# DIDV_-_Alto_Falantes.net
KiCad netlist of a schematic drawn in EAGLE
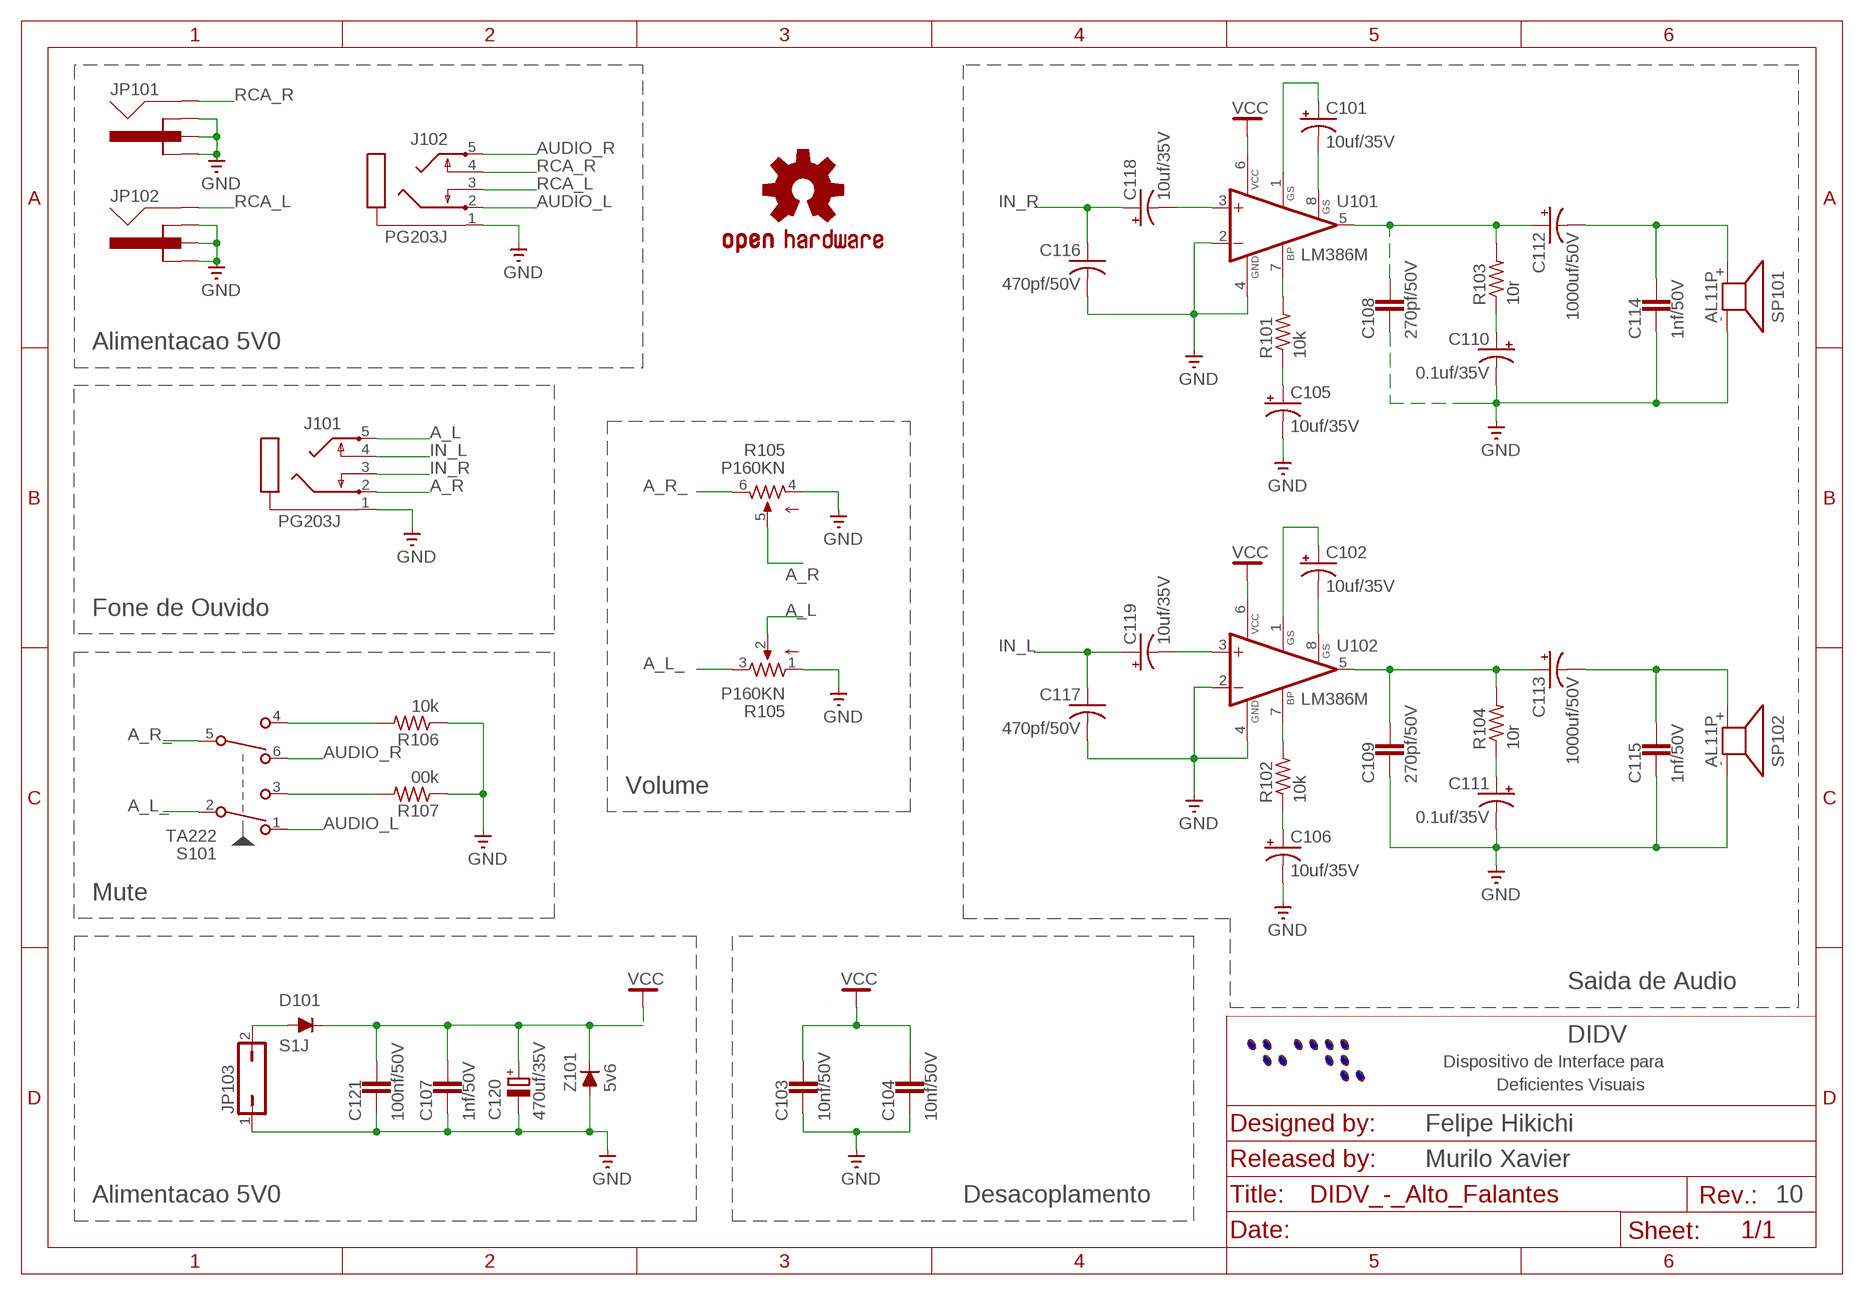
[diagram p0: schematic, sheet 1]

(export (version "E")
  (design (tool "Eeschema 10.0.6"))
  (components
    (comp (ref "C101")
      (value "10uf/35V")
      (footprint "eagle-import:E2-5")
      (libsource (lib "eagle-import") (part "CPOL-USE2-5"))
    )
    (comp (ref "C102")
      (value "10uf/35V")
      (footprint "eagle-import:E2-5")
      (libsource (lib "eagle-import") (part "CPOL-USE2-5"))
    )
    (comp (ref "C103")
      (value "10nf/50V")
      (footprint "eagle-import:C0805")
      (libsource (lib "eagle-import") (part "C-EUC0805"))
    )
    (comp (ref "C104")
      (value "10nf/50V")
      (footprint "eagle-import:C0805")
      (libsource (lib "eagle-import") (part "C-EUC0805"))
    )
    (comp (ref "C105")
      (value "10uf/35V")
      (footprint "eagle-import:E2-5")
      (libsource (lib "eagle-import") (part "CPOL-USE2-5"))
    )
    (comp (ref "C106")
      (value "10uf/35V")
      (footprint "eagle-import:E2-5")
      (libsource (lib "eagle-import") (part "CPOL-USE2-5"))
    )
    (comp (ref "C107")
      (value "1nf/50V")
      (footprint "eagle-import:C0805")
      (libsource (lib "eagle-import") (part "C-EUC0805"))
    )
    (comp (ref "C108")
      (value "270pf/50V")
      (footprint "eagle-import:C0805")
      (libsource (lib "eagle-import") (part "C-EUC0805"))
    )
    (comp (ref "C109")
      (value "270pf/50V")
      (footprint "eagle-import:C0805")
      (libsource (lib "eagle-import") (part "C-EUC0805"))
    )
    (comp (ref "C110")
      (value "0.1uf/35V")
      (footprint "eagle-import:E2-5")
      (libsource (lib "eagle-import") (part "CPOL-USE2-5"))
    )
    (comp (ref "C111")
      (value "0.1uf/35V")
      (footprint "eagle-import:E2-5")
      (libsource (lib "eagle-import") (part "CPOL-USE2-5"))
    )
    (comp (ref "C112")
      (value "1000uf/50V")
      (footprint "eagle-import:E3,5-10")
      (libsource (lib "eagle-import") (part "CPOL-USE3.5-10"))
    )
    (comp (ref "C113")
      (value "1000uf/50V")
      (footprint "eagle-import:E3,5-10")
      (libsource (lib "eagle-import") (part "CPOL-USE3.5-10"))
    )
    (comp (ref "C114")
      (value "1nf/50V")
      (footprint "eagle-import:C0805")
      (libsource (lib "eagle-import") (part "C-EUC0805"))
    )
    (comp (ref "C115")
      (value "1nf/50V")
      (footprint "eagle-import:C0805")
      (libsource (lib "eagle-import") (part "C-EUC0805"))
    )
    (comp (ref "C116")
      (value "470pf/50V")
      (footprint "eagle-import:C0603")
      (libsource (lib "eagle-import") (part "C-USC0603"))
    )
    (comp (ref "C117")
      (value "470pf/50V")
      (footprint "eagle-import:C0603")
      (libsource (lib "eagle-import") (part "C-USC0603"))
    )
    (comp (ref "C118")
      (value "10uf/35V")
      (footprint "eagle-import:E2-5")
      (libsource (lib "eagle-import") (part "CPOL-USE2-5"))
    )
    (comp (ref "C119")
      (value "10uf/35V")
      (footprint "eagle-import:E2-5")
      (libsource (lib "eagle-import") (part "CPOL-USE2-5"))
    )
    (comp (ref "C120")
      (value "470uf/35V")
      (footprint "eagle-import:E3,5-10")
      (libsource (lib "eagle-import") (part "CPOL-EUE3.5-10"))
    )
    (comp (ref "C121")
      (value "100nf/50V")
      (footprint "eagle-import:C0805")
      (libsource (lib "eagle-import") (part "C-EUC0805"))
    )
    (comp (ref "D101")
      (value "S1J")
      (footprint "eagle-import:DO214AC")
      (libsource (lib "eagle-import") (part "FS1J"))
    )
    (comp (ref "J101")
      (value "PG203J")
      (footprint "eagle-import:PG203J")
      (libsource (lib "eagle-import") (part "PG203J"))
    )
    (comp (ref "J102")
      (value "PG203J")
      (footprint "eagle-import:PG203J")
      (libsource (lib "eagle-import") (part "PG203J"))
    )
    (comp (ref "JP101")
      (value "RCA")
      (footprint "eagle-import:RCA")
      (libsource (lib "eagle-import") (part "RCA"))
    )
    (comp (ref "JP102")
      (value "RCA")
      (footprint "eagle-import:RCA")
      (libsource (lib "eagle-import") (part "RCA"))
    )
    (comp (ref "JP103")
      (value "JP1Q")
      (footprint "eagle-import:JP1")
      (libsource (lib "eagle-import") (part "JP1Q"))
    )
    (comp (ref "LOGO101")
      (value "OSHW-LOGOL")
      (footprint "eagle-import:OSHW-LOGO-L")
      (libsource (lib "eagle-import") (part "OSHW-LOGOL"))
    )
    (comp (ref "R101")
      (value "10k")
      (footprint "eagle-import:R1206")
      (libsource (lib "eagle-import") (part "R-US_R1206"))
    )
    (comp (ref "R102")
      (value "10k")
      (footprint "eagle-import:R1206")
      (libsource (lib "eagle-import") (part "R-US_R1206"))
    )
    (comp (ref "R103")
      (value "10r")
      (footprint "eagle-import:R1206")
      (libsource (lib "eagle-import") (part "R-US_R1206"))
    )
    (comp (ref "R104")
      (value "10r")
      (footprint "eagle-import:R1206")
      (libsource (lib "eagle-import") (part "R-US_R1206"))
    )
    (comp (ref "R105")
      (value "P160KN")
      (footprint "eagle-import:P160KN")
      (libsource (lib "eagle-import") (part "P160KN"))
    )
    (comp (ref "R106")
      (value "10k")
      (footprint "eagle-import:R1206")
      (libsource (lib "eagle-import") (part "R-US_R1206"))
    )
    (comp (ref "R107")
      (value "00k")
      (footprint "eagle-import:R1206")
      (libsource (lib "eagle-import") (part "R-US_R1206"))
    )
    (comp (ref "S101")
      (value "TA222")
      (footprint "eagle-import:TA222")
      (libsource (lib "eagle-import") (part "TA222"))
    )
    (comp (ref "SP101")
      (value "AL11P")
      (footprint "eagle-import:AL11P")
      (libsource (lib "eagle-import") (part "AL11P"))
    )
    (comp (ref "SP102")
      (value "AL11P")
      (footprint "eagle-import:AL11P")
      (libsource (lib "eagle-import") (part "AL11P"))
    )
    (comp (ref "U101")
      (value "LM386M")
      (footprint "eagle-import:SO08")
      (libsource (lib "eagle-import") (part "LM386M"))
    )
    (comp (ref "U102")
      (value "LM386M")
      (footprint "eagle-import:SO08")
      (libsource (lib "eagle-import") (part "LM386M"))
    )
    (comp (ref "Z101")
      (value "5v6")
      (footprint "eagle-import:SOT23")
      (libsource (lib "eagle-import") (part "BAS70"))
    )
  )
  (nets
    (net (code "1") (name "/AUDIO_L") (class "Default")
      (node (ref "J102") (pin "2") (pinfunction "2_2") (pintype "passive"))
      (node (ref "S101") (pin "1") (pinfunction "A-NC_1") (pintype "passive"))
    )
    (net (code "2") (name "/AUDIO_R") (class "Default")
      (node (ref "J102") (pin "5") (pinfunction "5_5") (pintype "passive"))
      (node (ref "S101") (pin "6") (pinfunction "B-NC_6") (pintype "passive"))
    )
    (net (code "3") (name "/A_L") (class "Default")
      (node (ref "J101") (pin "5") (pinfunction "5_5") (pintype "passive"))
      (node (ref "R105") (pin "2") (pinfunction "2_2") (pintype "passive"))
    )
    (net (code "4") (name "/A_L_") (class "Default")
      (node (ref "R105") (pin "3") (pinfunction "3_3") (pintype "passive"))
      (node (ref "S101") (pin "2") (pinfunction "A-COM_2") (pintype "passive"))
    )
    (net (code "5") (name "/A_R") (class "Default")
      (node (ref "J101") (pin "2") (pinfunction "2_2") (pintype "passive"))
      (node (ref "R105") (pin "5") (pinfunction "6_5") (pintype "passive"))
    )
    (net (code "6") (name "/A_R_") (class "Default")
      (node (ref "R105") (pin "6") (pinfunction "5_6") (pintype "passive"))
      (node (ref "S101") (pin "5") (pinfunction "B-COM_5") (pintype "passive"))
    )
    (net (code "7") (name "/IN_L") (class "Default")
      (node (ref "C117") (pin "1") (pinfunction "1_1") (pintype "passive"))
      (node (ref "C119") (pin "+") (pinfunction "+_+") (pintype "passive"))
      (node (ref "J101") (pin "4") (pinfunction "4_4") (pintype "passive"))
    )
    (net (code "8") (name "/IN_R") (class "Default")
      (node (ref "C116") (pin "1") (pinfunction "1_1") (pintype "passive"))
      (node (ref "C118") (pin "+") (pinfunction "+_+") (pintype "passive"))
      (node (ref "J101") (pin "3") (pinfunction "3_3") (pintype "passive"))
    )
    (net (code "9") (name "/RCA_L") (class "Default")
      (node (ref "J102") (pin "3") (pinfunction "3_3") (pintype "passive"))
      (node (ref "JP102") (pin "_SIGNAL") (pinfunction "SIGNAL__SIGNAL") (pintype "bidirectional"))
    )
    (net (code "10") (name "/RCA_R") (class "Default")
      (node (ref "J102") (pin "4") (pinfunction "4_4") (pintype "passive"))
      (node (ref "JP101") (pin "_SIGNAL") (pinfunction "SIGNAL__SIGNAL") (pintype "bidirectional"))
    )
    (net (code "11") (name "GND") (class "Default")
      (node (ref "C103") (pin "2") (pinfunction "2_2") (pintype "passive"))
      (node (ref "C104") (pin "2") (pinfunction "2_2") (pintype "passive"))
      (node (ref "C105") (pin "-") (pinfunction "-_-") (pintype "passive"))
      (node (ref "C106") (pin "-") (pinfunction "-_-") (pintype "passive"))
      (node (ref "C107") (pin "2") (pinfunction "2_2") (pintype "passive"))
      (node (ref "C108") (pin "2") (pinfunction "2_2") (pintype "passive"))
      (node (ref "C109") (pin "2") (pinfunction "2_2") (pintype "passive"))
      (node (ref "C110") (pin "-") (pinfunction "-_-") (pintype "passive"))
      (node (ref "C111") (pin "-") (pinfunction "-_-") (pintype "passive"))
      (node (ref "C114") (pin "2") (pinfunction "2_2") (pintype "passive"))
      (node (ref "C115") (pin "2") (pinfunction "2_2") (pintype "passive"))
      (node (ref "C116") (pin "2") (pinfunction "2_2") (pintype "passive"))
      (node (ref "C117") (pin "2") (pinfunction "2_2") (pintype "passive"))
      (node (ref "C120") (pin "-") (pinfunction "-_-") (pintype "passive"))
      (node (ref "C121") (pin "2") (pinfunction "2_2") (pintype "passive"))
      (node (ref "J101") (pin "1") (pinfunction "1_1") (pintype "passive"))
      (node (ref "J102") (pin "1") (pinfunction "1_1") (pintype "passive"))
      (node (ref "JP101") (pin "_1GND") (pinfunction "GND1__1GND") (pintype "bidirectional"))
      (node (ref "JP101") (pin "_2GND") (pinfunction "GND2__2GND") (pintype "bidirectional"))
      (node (ref "JP101") (pin "_GND") (pinfunction "GND__GND") (pintype "bidirectional"))
      (node (ref "JP102") (pin "_1GND") (pinfunction "GND1__1GND") (pintype "bidirectional"))
      (node (ref "JP102") (pin "_2GND") (pinfunction "GND2__2GND") (pintype "bidirectional"))
      (node (ref "JP102") (pin "_GND") (pinfunction "GND__GND") (pintype "bidirectional"))
      (node (ref "JP103") (pin "1") (pinfunction "1_1") (pintype "passive"))
      (node (ref "R105") (pin "1") (pinfunction "1_1") (pintype "passive"))
      (node (ref "R105") (pin "4") (pinfunction "4_4") (pintype "passive"))
      (node (ref "R106") (pin "1") (pinfunction "1_1") (pintype "passive"))
      (node (ref "R107") (pin "1") (pinfunction "1_1") (pintype "passive"))
      (node (ref "SP101") (pin "-") (pinfunction "1_-") (pintype "passive"))
      (node (ref "SP102") (pin "-") (pinfunction "1_-") (pintype "passive"))
      (node (ref "U101") (pin "2") (pinfunction "-IN_2") (pintype "input"))
      (node (ref "U101") (pin "4") (pinfunction "GND_4") (pintype "power_in"))
      (node (ref "U102") (pin "2") (pinfunction "-IN_2") (pintype "input"))
      (node (ref "U102") (pin "4") (pinfunction "GND_4") (pintype "power_in"))
      (node (ref "Z101") (pin "1") (pinfunction "A_1") (pintype "passive"))
    )
    (net (code "12") (name "Net-(C101-Pad+)") (class "Default")
      (node (ref "C101") (pin "+") (pinfunction "+_+") (pintype "passive"))
      (node (ref "U101") (pin "1") (pinfunction "GAIN_1") (pintype "passive"))
    )
    (net (code "13") (name "Net-(C101-Pad-)") (class "Default")
      (node (ref "C101") (pin "-") (pinfunction "-_-") (pintype "passive"))
      (node (ref "U101") (pin "8") (pinfunction "GAIN_8") (pintype "passive"))
    )
    (net (code "14") (name "Net-(C102-Pad+)") (class "Default")
      (node (ref "C102") (pin "+") (pinfunction "+_+") (pintype "passive"))
      (node (ref "U102") (pin "1") (pinfunction "GAIN_1") (pintype "passive"))
    )
    (net (code "15") (name "Net-(C102-Pad-)") (class "Default")
      (node (ref "C102") (pin "-") (pinfunction "-_-") (pintype "passive"))
      (node (ref "U102") (pin "8") (pinfunction "GAIN_8") (pintype "passive"))
    )
    (net (code "16") (name "Net-(C105-Pad+)") (class "Default")
      (node (ref "C105") (pin "+") (pinfunction "+_+") (pintype "passive"))
      (node (ref "R101") (pin "1") (pinfunction "1_1") (pintype "passive"))
    )
    (net (code "17") (name "Net-(C106-Pad+)") (class "Default")
      (node (ref "C106") (pin "+") (pinfunction "+_+") (pintype "passive"))
      (node (ref "R102") (pin "1") (pinfunction "1_1") (pintype "passive"))
    )
    (net (code "18") (name "Net-(C110-Pad+)") (class "Default")
      (node (ref "C110") (pin "+") (pinfunction "+_+") (pintype "passive"))
      (node (ref "R103") (pin "1") (pinfunction "1_1") (pintype "passive"))
    )
    (net (code "19") (name "Net-(C111-Pad+)") (class "Default")
      (node (ref "C111") (pin "+") (pinfunction "+_+") (pintype "passive"))
      (node (ref "R104") (pin "1") (pinfunction "1_1") (pintype "passive"))
    )
    (net (code "20") (name "Net-(D101-PadA)") (class "Default")
      (node (ref "D101") (pin "A") (pinfunction "A_A") (pintype "passive"))
      (node (ref "JP103") (pin "2") (pinfunction "2_2") (pintype "passive"))
    )
    (net (code "21") (name "Net-(S101-A-NO)") (class "Default")
      (node (ref "R107") (pin "2") (pinfunction "2_2") (pintype "passive"))
      (node (ref "S101") (pin "3") (pinfunction "A-NO_3") (pintype "passive"))
    )
    (net (code "22") (name "Net-(S101-B-NO)") (class "Default")
      (node (ref "R106") (pin "2") (pinfunction "2_2") (pintype "passive"))
      (node (ref "S101") (pin "4") (pinfunction "B-NO_4") (pintype "passive"))
    )
    (net (code "23") (name "Net-(SP101-2)") (class "Default")
      (node (ref "C112") (pin "-") (pinfunction "-_-") (pintype "passive"))
      (node (ref "C114") (pin "1") (pinfunction "1_1") (pintype "passive"))
      (node (ref "SP101") (pin "+") (pinfunction "2_+") (pintype "passive"))
    )
    (net (code "24") (name "Net-(SP102-2)") (class "Default")
      (node (ref "C113") (pin "-") (pinfunction "-_-") (pintype "passive"))
      (node (ref "C115") (pin "1") (pinfunction "1_1") (pintype "passive"))
      (node (ref "SP102") (pin "+") (pinfunction "2_+") (pintype "passive"))
    )
    (net (code "25") (name "Net-(U101-+IN)") (class "Default")
      (node (ref "C118") (pin "-") (pinfunction "-_-") (pintype "passive"))
      (node (ref "U101") (pin "3") (pinfunction "+IN_3") (pintype "input"))
    )
    (net (code "26") (name "Net-(U101-BS2)") (class "Default")
      (node (ref "R101") (pin "2") (pinfunction "2_2") (pintype "passive"))
      (node (ref "U101") (pin "7") (pinfunction "BS2_7") (pintype "passive"))
    )
    (net (code "27") (name "Net-(U101-OUT)") (class "Default")
      (node (ref "C108") (pin "1") (pinfunction "1_1") (pintype "passive"))
      (node (ref "C112") (pin "+") (pinfunction "+_+") (pintype "passive"))
      (node (ref "R103") (pin "2") (pinfunction "2_2") (pintype "passive"))
      (node (ref "U101") (pin "5") (pinfunction "OUT_5") (pintype "output"))
    )
    (net (code "28") (name "Net-(U102-+IN)") (class "Default")
      (node (ref "C119") (pin "-") (pinfunction "-_-") (pintype "passive"))
      (node (ref "U102") (pin "3") (pinfunction "+IN_3") (pintype "input"))
    )
    (net (code "29") (name "Net-(U102-BS2)") (class "Default")
      (node (ref "R102") (pin "2") (pinfunction "2_2") (pintype "passive"))
      (node (ref "U102") (pin "7") (pinfunction "BS2_7") (pintype "passive"))
    )
    (net (code "30") (name "Net-(U102-OUT)") (class "Default")
      (node (ref "C109") (pin "1") (pinfunction "1_1") (pintype "passive"))
      (node (ref "C113") (pin "+") (pinfunction "+_+") (pintype "passive"))
      (node (ref "R104") (pin "2") (pinfunction "2_2") (pintype "passive"))
      (node (ref "U102") (pin "5") (pinfunction "OUT_5") (pintype "output"))
    )
    (net (code "31") (name "VCC") (class "Default")
      (node (ref "C103") (pin "1") (pinfunction "1_1") (pintype "passive"))
      (node (ref "C104") (pin "1") (pinfunction "1_1") (pintype "passive"))
      (node (ref "C107") (pin "1") (pinfunction "1_1") (pintype "passive"))
      (node (ref "C120") (pin "+") (pinfunction "+_+") (pintype "passive"))
      (node (ref "C121") (pin "1") (pinfunction "1_1") (pintype "passive"))
      (node (ref "D101") (pin "C") (pinfunction "C_C") (pintype "passive"))
      (node (ref "U101") (pin "6") (pinfunction "VS_6") (pintype "power_in"))
      (node (ref "U102") (pin "6") (pinfunction "VS_6") (pintype "power_in"))
      (node (ref "Z101") (pin "3") (pinfunction "C_3") (pintype "passive"))
    )
  )
)
